# ST-LinkV2.net
KiCad netlist of a schematic drawn in Altium Designer
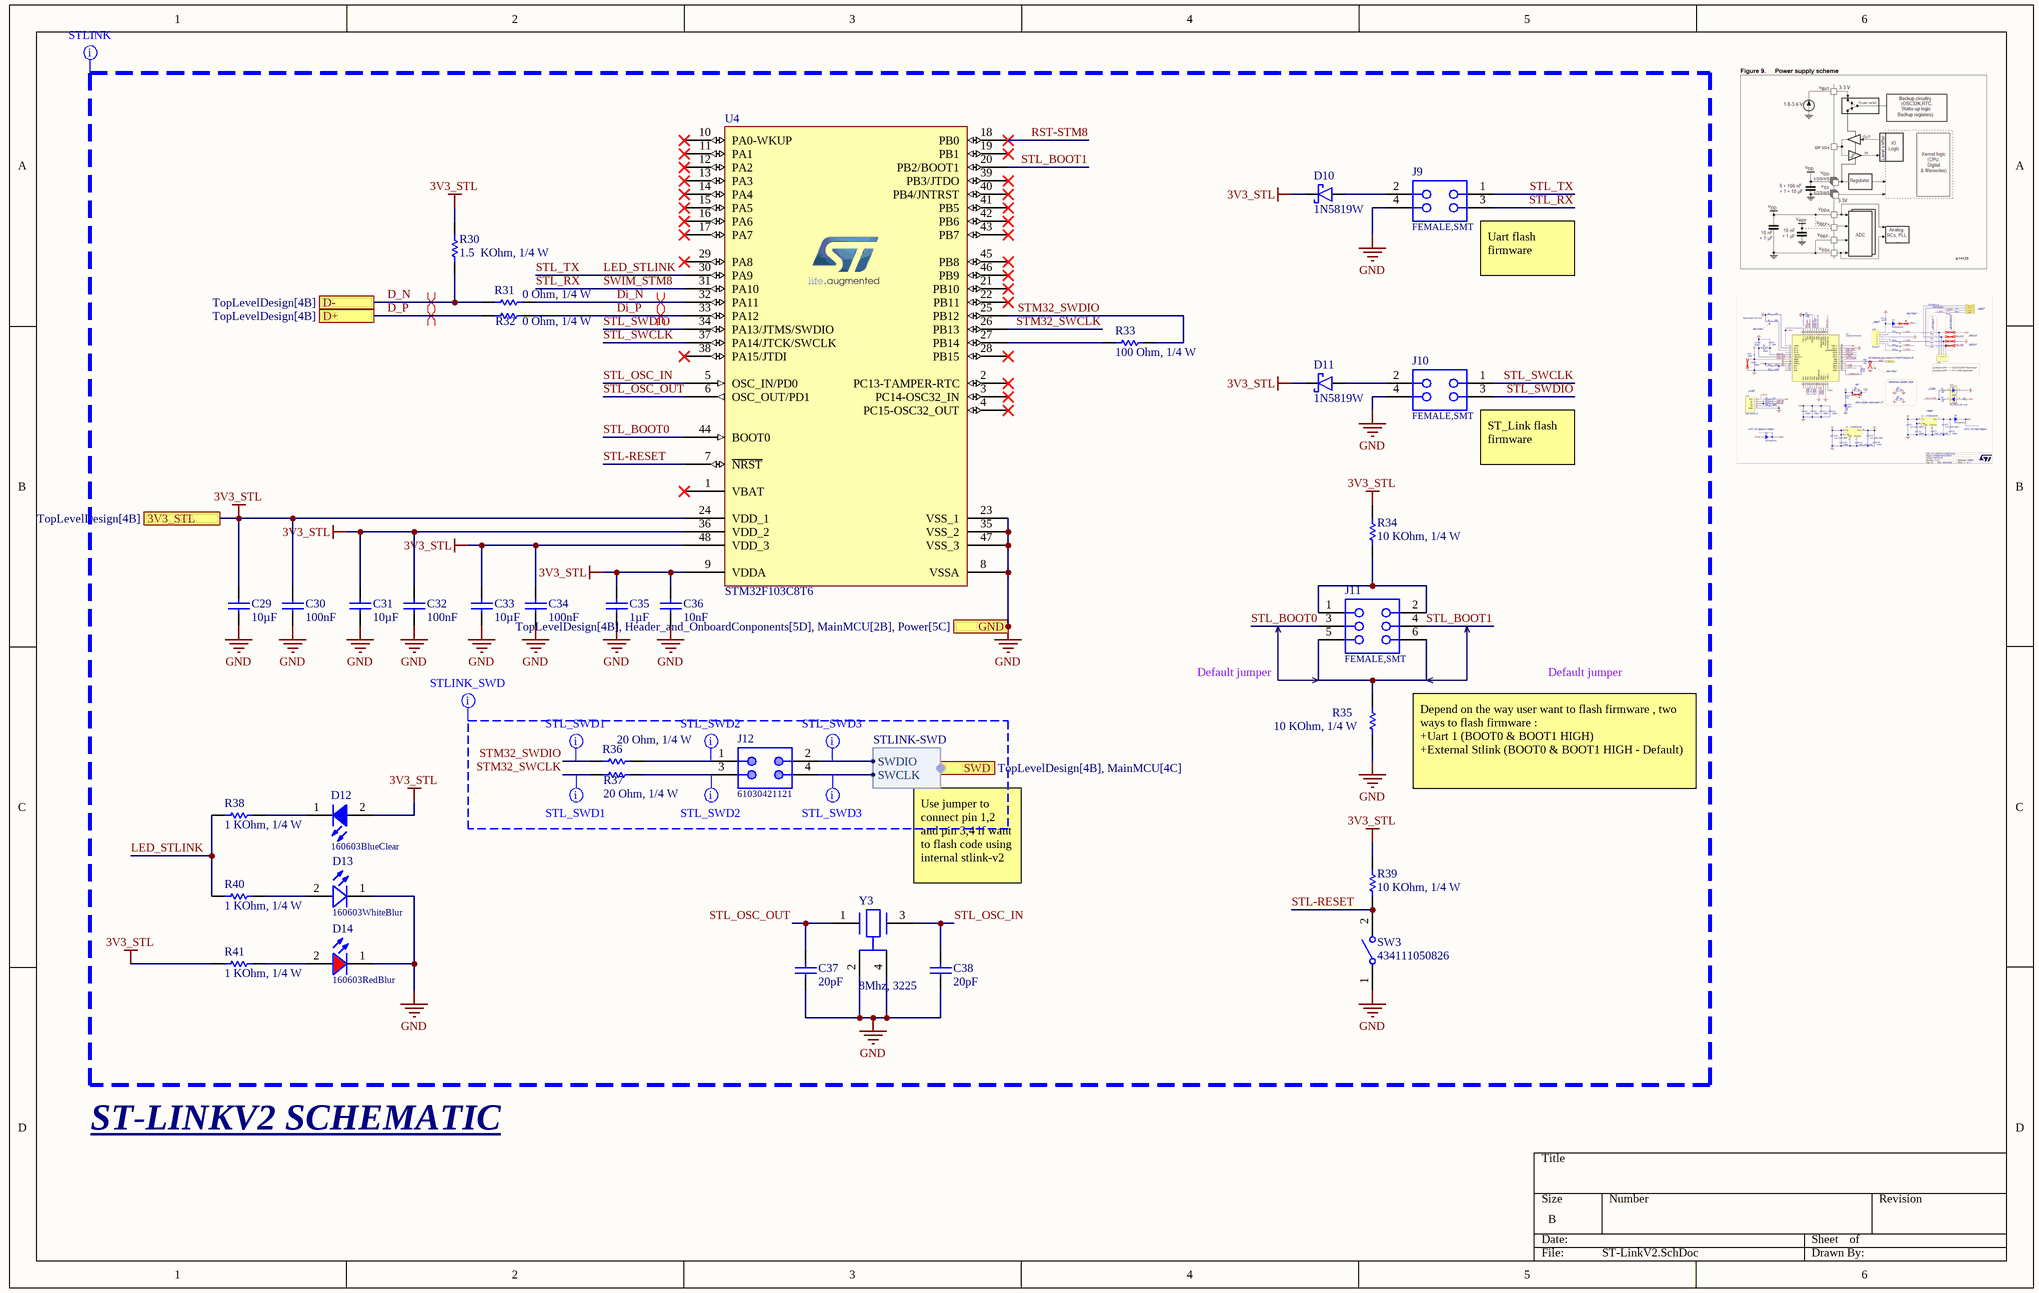
[diagram p0: ST-LinkV2.SchDoc]

(export (version "E")
  (design (tool "Eeschema 10.0.6"))
  (components
    (comp (ref "C29")
      (value "10µF")
      (footprint "CAP_0603")
      (description "CAP, size 0603, 10 uF, 10 VDC")
      (fields
        (field (name "TOLERANCE") "10%")
        (field (name "Comment") "0106031061010")
        (field (name "SOURCE") "Capacitor_0603_10_percent.SchLib")
      )
      (libsource (lib "Tin Tran") (part "010603475106.3"))
    )
    (comp (ref "C30")
      (value "100nF")
      (footprint "CAP_0603")
      (description "CAP, size 0603, 100 nF, 50 VDC")
      (fields
        (field (name "TOLERANCE") "10%")
        (field (name "Comment") "0106031041050")
        (field (name "SOURCE") "Capacitor_0603_10_percent.SchLib")
      )
      (libsource (lib "Tin Tran") (part "010603475106.3"))
    )
    (comp (ref "C31")
      (value "10µF")
      (footprint "CAP_0603")
      (description "CAP, size 0603, 10 uF, 10 VDC")
      (fields
        (field (name "TOLERANCE") "10%")
        (field (name "Comment") "0106031061010")
        (field (name "SOURCE") "Capacitor_0603_10_percent.SchLib")
      )
      (libsource (lib "Tin Tran") (part "010603475106.3"))
    )
    (comp (ref "C32")
      (value "100nF")
      (footprint "CAP_0603")
      (description "CAP, size 0603, 100 nF, 50 VDC")
      (fields
        (field (name "TOLERANCE") "10%")
        (field (name "Comment") "0106031041050")
        (field (name "SOURCE") "Capacitor_0603_10_percent.SchLib")
      )
      (libsource (lib "Tin Tran") (part "010603475106.3"))
    )
    (comp (ref "C33")
      (value "10µF")
      (footprint "CAP_0603")
      (description "CAP, size 0603, 10 uF, 10 VDC")
      (fields
        (field (name "TOLERANCE") "10%")
        (field (name "Comment") "0106031061010")
        (field (name "SOURCE") "Capacitor_0603_10_percent.SchLib")
      )
      (libsource (lib "Tin Tran") (part "010603475106.3"))
    )
    (comp (ref "C34")
      (value "100nF")
      (footprint "CAP_0603")
      (description "CAP, size 0603, 100 nF, 50 VDC")
      (fields
        (field (name "TOLERANCE") "10%")
        (field (name "Comment") "0106031041050")
        (field (name "SOURCE") "Capacitor_0603_10_percent.SchLib")
      )
      (libsource (lib "Tin Tran") (part "010603475106.3"))
    )
    (comp (ref "C35")
      (value "1µF")
      (footprint "CAP_0603")
      (description "CAP, size 0603, 1 uF, 16 VDC")
      (fields
        (field (name "TOLERANCE") "10%")
        (field (name "Comment") "0106031051016")
        (field (name "SOURCE") "Capacitor_0603_10_percent.SchLib")
      )
      (libsource (lib "Tin Tran") (part "010603475106.3"))
    )
    (comp (ref "C36")
      (value "10nF")
      (footprint "CAP_0603")
      (description "CAP, size 0603, 10 nF, 50 VDC")
      (fields
        (field (name "TOLERANCE") "5%")
        (field (name "Comment") "0106031030550")
        (field (name "SOURCE") "Capacitor_0603_5_percent.SchLib")
      )
      (libsource (lib "Tin Tran") (part "0106036820550"))
    )
    (comp (ref "C37")
      (value "20pF")
      (footprint "CAP_0603")
      (description "CAP, size 0603, 20 pF, 50 VDC")
      (fields
        (field (name "TOLERANCE") "5%")
        (field (name "Comment") "0106031000550")
        (field (name "SOURCE") "Capacitor_0603_5_percent.SchLib")
      )
      (libsource (lib "Tin Tran") (part "0106036820550"))
    )
    (comp (ref "C38")
      (value "20pF")
      (footprint "CAP_0603")
      (description "CAP, size 0603, 20 pF, 50 VDC")
      (fields
        (field (name "TOLERANCE") "5%")
        (field (name "Comment") "0106031000550")
        (field (name "SOURCE") "Capacitor_0603_5_percent.SchLib")
      )
      (libsource (lib "Tin Tran") (part "0106036820550"))
    )
    (comp (ref "D10") (value "1N5819W") (footprint "1N5819W") (libsource (lib "Tin Tran") (part "1N5819W")))
    (comp (ref "D11") (value "1N5819W") (footprint "1N5819W") (libsource (lib "Tin Tran") (part "1N5819W")))
    (comp (ref "D12")
      (value "160603BlueClear")
      (footprint "WL-SMCW_0603_H=0.7mm")
      (description "WL-SMCW SMT Mono-color Chip LED Waterclear, size 0603, Blue, 3.2V, 140deg")
      (libsource (lib "Tin Tran") (part "160603BlueClear"))
    )
    (comp (ref "D13")
      (value "160603WhiteBlur")
      (footprint "WL-SMCW_0603_H=0.7mm")
      (description "WL-SMCW SMT Mono-color Chip LED Blur, size 0603, White")
      (libsource (lib "Tin Tran") (part "160603WhiteClear"))
    )
    (comp (ref "D14")
      (value "160603RedBlur")
      (footprint "WL-SMCW_0603_H=0.7mm")
      (description "WL-SMCW SMT Mono-color Chip LED Blur, size 0603, Red, 2V, 140deg")
      (libsource (lib "Tin Tran") (part "160603RedClear"))
    )
    (comp (ref "J9")
      (value "FEMALE,SMT")
      (footprint "61000421821")
      (description "WR-PHD Socket Header, SMT, pitch 2.54mm, Dual Row, Vertical, 4p")
      (fields
        (field (name "MANUFACTURER") "Wurth Elektronik")
        (field (name "MANUFACTURER PART NUMBER") "61000421821")
      )
      (libsource (lib "Tin Tran") (part "61000421821"))
    )
    (comp (ref "J10")
      (value "FEMALE,SMT")
      (footprint "61000421821")
      (description "WR-PHD Socket Header, SMT, pitch 2.54mm, Dual Row, Vertical, 4p")
      (fields
        (field (name "MANUFACTURER") "Wurth Elektronik")
        (field (name "MANUFACTURER PART NUMBER") "61000421821")
      )
      (libsource (lib "Tin Tran") (part "61000421821"))
    )
    (comp (ref "J11")
      (value "FEMALE,SMT")
      (footprint "61030621821")
      (description "WR-PHD Socket Header, SMT, pitch 2.54mm, Dual Row, Vertical, 6p")
      (fields
        (field (name "MANUFACTURER PART NUMBER") "61030621821")
        (field (name "MANUFACTURER") "Wurth Elektronik")
      )
      (libsource (lib "Tin Tran") (part "613006243121"))
    )
    (comp (ref "J12")
      (value "61030421121")
      (footprint "61030421121")
      (description "WR-PHD Pin Header, SMT, pitch 2.54mm, Dual Row, Vertical, 4p")
      (fields (field (name "MANUFACTURER") "Wurth Elektronik"))
      (libsource (lib "Tin Tran") (part "61300421121"))
    )
    (comp (ref "R30")
      (value "1.5  KOhm, 1/4 W")
      (footprint "resistor_0603")
      (description "RES, size 0603, 1.5  KOhm, 1/4 W")
      (fields (field (name "Comment") "0006031521"))
      (libsource (lib "Tin Tran") (part "00060371541"))
    )
    (comp (ref "R31")
      (value "0 Ohm, 1/4 W")
      (footprint "resistor_0603")
      (description "RES, size 0603, 0 Ohm, 1/4 W")
      (fields (field (name "Comment") "0006030001"))
      (libsource (lib "Tin Tran") (part "00060371541"))
    )
    (comp (ref "R32")
      (value "0 Ohm, 1/4 W")
      (footprint "resistor_0603")
      (description "RES, size 0603, 0 Ohm, 1/4 W")
      (fields (field (name "Comment") "0006030001"))
      (libsource (lib "Tin Tran") (part "00060371541"))
    )
    (comp (ref "R33")
      (value "100 Ohm, 1/4 W")
      (footprint "resistor_0603")
      (description "RES, size 0603, 100 Ohm, 1/4 W")
      (fields (field (name "Comment") "0006031011"))
      (libsource (lib "Tin Tran") (part "00060371541"))
    )
    (comp (ref "R34")
      (value "10 KOhm, 1/4 W")
      (footprint "resistor_0603")
      (description "RES, size 0603, 10 KOhm, 1/4 W")
      (fields (field (name "Comment") "0006031031"))
      (libsource (lib "Tin Tran") (part "00060371541"))
    )
    (comp (ref "R35")
      (value "10 KOhm, 1/4 W")
      (footprint "resistor_0603")
      (description "RES, size 0603, 10 KOhm, 1/4 W")
      (fields (field (name "Comment") "0006031031"))
      (libsource (lib "Tin Tran") (part "00060371541"))
    )
    (comp (ref "R36")
      (value "20 Ohm, 1/4 W")
      (footprint "resistor_0603")
      (description "RES, size 0603, 20 Ohm, 1/4 W")
      (fields (field (name "Comment") "0006032001"))
      (libsource (lib "Tin Tran") (part "00060371541"))
    )
    (comp (ref "R37")
      (value "20 Ohm, 1/4 W")
      (footprint "resistor_0603")
      (description "RES, size 0603, 20 Ohm, 1/4 W")
      (fields (field (name "Comment") "0006032001"))
      (libsource (lib "Tin Tran") (part "00060371541"))
    )
    (comp (ref "R38")
      (value "1 KOhm, 1/4 W")
      (footprint "resistor_0603")
      (description "RES, size 0603, 1 KOhm, 1/4 W")
      (fields (field (name "Comment") "0006031021"))
      (libsource (lib "Tin Tran") (part "00060371541"))
    )
    (comp (ref "R39")
      (value "10 KOhm, 1/4 W")
      (footprint "resistor_0603")
      (description "RES, size 0603, 10 KOhm, 1/4 W")
      (fields (field (name "Comment") "0006031031"))
      (libsource (lib "Tin Tran") (part "00060371541"))
    )
    (comp (ref "R40")
      (value "1 KOhm, 1/4 W")
      (footprint "resistor_0603")
      (description "RES, size 0603, 1 KOhm, 1/4 W")
      (fields (field (name "Comment") "0006031021"))
      (libsource (lib "Tin Tran") (part "00060371541"))
    )
    (comp (ref "R41")
      (value "1 KOhm, 1/4 W")
      (footprint "resistor_0603")
      (description "RES, size 0603, 1 KOhm, 1/4 W")
      (fields (field (name "Comment") "0006031021"))
      (libsource (lib "Tin Tran") (part "00060371541"))
    )
    (comp (ref "SW3")
      (value "434111050826")
      (footprint "WS-TASV_L6W3.5H5_4341x10508x6")
      (description "WS-TASV SMT Tact Switch, L6 x W3.5 x H5mm, 260g, SPST-NO, 12V, 50mA")
      (fields (field (name "MANUFACTURER") "Wurth Elektronik"))
      (libsource (lib "Tin Tran") (part "434111050826"))
    )
    (comp (ref "U4")
      (value "STM32F103C8T6")
      (footprint "STM32F103C8T6")
      (description "ARM Microcontrollers - MCU 32BIT Cortex M3 64KB 20KB RAM 2X12 ADC")
      (fields (field (name "MANUFACTURER") "STM"))
      (libsource (lib "Tin Tran") (part "STM32F103C8T6"))
    )
    (comp (ref "Y3")
      (value "8Mhz, 3225")
      (footprint "FP-NX3225SA-MFG")
      (description "CRYSTAL 25.0000MHZ 8PF SMD")
      (fields
        (field (name "OCTOPART") "https://octopart.com/nx3225sa-25.000m-std-crs-2-ndk-51374293")
        (field (name "TOLERANCE") "15ppm")
      )
      (libsource (lib "Tin Tran") (part "CMP-200220-000002-1"))
    )
  )
  (nets
    (net (code "2") (name "/D_N") (class "Default")
      (node (ref "R30") (pin "1") (pinfunction "1_1") (pintype "passive"))
      (node (ref "R31") (pin "1") (pinfunction "1_1") (pintype "passive"))
    )
    (net (code "3") (name "/D_P") (class "Default")
      (node (ref "R32") (pin "1") (pinfunction "1_1") (pintype "passive"))
    )
    (net (code "4") (name "/Di_N") (class "Default")
      (node (ref "R31") (pin "2") (pinfunction "2_2") (pintype "passive"))
      (node (ref "U4") (pin "32") (pinfunction "PA11_32") (pintype "bidirectional"))
    )
    (net (code "5") (name "/Di_P") (class "Default")
      (node (ref "R32") (pin "2") (pinfunction "2_2") (pintype "passive"))
      (node (ref "U4") (pin "33") (pinfunction "PA12_33") (pintype "bidirectional"))
    )
    (net (code "6") (name "/LED_STLINK") (class "Default")
      (node (ref "J9") (pin "1") (pinfunction "1_1") (pintype "passive"))
      (node (ref "R38") (pin "1") (pinfunction "1_1") (pintype "passive"))
      (node (ref "R40") (pin "1") (pinfunction "1_1") (pintype "passive"))
      (node (ref "U4") (pin "30") (pinfunction "PA9_30") (pintype "bidirectional"))
    )
    (net (code "7") (name "/RST-STM8") (class "Default")
      (node (ref "U4") (pin "18") (pinfunction "PB0_18") (pintype "bidirectional+no_connect"))
    )
    (net (code "8") (name "/STL-RESET") (class "Default")
      (node (ref "R39") (pin "1") (pinfunction "1_1") (pintype "passive"))
      (node (ref "SW3") (pin "2") (pinfunction "2_2") (pintype "passive"))
      (node (ref "U4") (pin "7") (pinfunction "~{NRST}_7") (pintype "bidirectional"))
    )
    (net (code "9") (name "/STL_BOOT0") (class "Default")
      (node (ref "J11") (pin "3") (pinfunction "3_3") (pintype "passive"))
      (node (ref "U4") (pin "44") (pinfunction "BOOT0_44") (pintype "input"))
    )
    (net (code "10") (name "/STL_BOOT1") (class "Default")
      (node (ref "J11") (pin "4") (pinfunction "4_4") (pintype "passive"))
      (node (ref "U4") (pin "20") (pinfunction "PB2/BOOT1_20") (pintype "bidirectional"))
    )
    (net (code "11") (name "/STL_OSC_IN") (class "Default")
      (node (ref "C38") (pin "2") (pinfunction "2_2") (pintype "passive"))
      (node (ref "U4") (pin "5") (pinfunction "OSC_IN/PD0_5") (pintype "input"))
      (node (ref "Y3") (pin "3") (pinfunction "3_3") (pintype "passive"))
    )
    (net (code "12") (name "/STL_OSC_OUT") (class "Default")
      (node (ref "C37") (pin "2") (pinfunction "2_2") (pintype "passive"))
      (node (ref "U4") (pin "6") (pinfunction "OSC_OUT/PD1_6") (pintype "output"))
      (node (ref "Y3") (pin "1") (pinfunction "1_1") (pintype "passive"))
    )
    (net (code "13") (name "/STL_RX") (class "Default")
      (node (ref "J9") (pin "3") (pinfunction "3_3") (pintype "passive"))
      (node (ref "U4") (pin "31") (pinfunction "PA10_31") (pintype "bidirectional"))
    )
    (net (code "14") (name "/STL_SWCLK") (class "Default")
      (node (ref "J10") (pin "1") (pinfunction "1_1") (pintype "passive"))
      (node (ref "U4") (pin "37") (pinfunction "PA14/JTCK/SWCLK_37") (pintype "bidirectional"))
    )
    (net (code "15") (name "/STL_SWDIO") (class "Default")
      (node (ref "J10") (pin "3") (pinfunction "3_3") (pintype "passive"))
      (node (ref "U4") (pin "34") (pinfunction "PA13/JTMS/SWDIO_34") (pintype "bidirectional"))
    )
    (net (code "16") (name "/STM32_SWCLK") (class "Default")
      (node (ref "R37") (pin "1") (pinfunction "1_1") (pintype "passive"))
      (node (ref "U4") (pin "26") (pinfunction "PB13_26") (pintype "bidirectional"))
    )
    (net (code "17") (name "/STM32_SWDIO") (class "Default")
      (node (ref "R33") (pin "1") (pinfunction "1_1") (pintype "passive"))
      (node (ref "R36") (pin "1") (pinfunction "1_1") (pintype "passive"))
      (node (ref "U4") (pin "25") (pinfunction "PB12_25") (pintype "bidirectional"))
    )
    (net (code "18") (name "/SWCLK") (class "Default")
      (node (ref "J12") (pin "4") (pinfunction "4_4") (pintype "passive"))
    )
    (net (code "19") (name "/SWDIO") (class "Default")
      (node (ref "J12") (pin "2") (pinfunction "2_2") (pintype "passive"))
    )
    (net (code "21") (name "3V3_STL") (class "Default")
      (node (ref "C29") (pin "2") (pinfunction "2_2") (pintype "passive"))
      (node (ref "C30") (pin "2") (pinfunction "2_2") (pintype "passive"))
      (node (ref "C31") (pin "2") (pinfunction "2_2") (pintype "passive"))
      (node (ref "C32") (pin "2") (pinfunction "2_2") (pintype "passive"))
      (node (ref "C33") (pin "2") (pinfunction "2_2") (pintype "passive"))
      (node (ref "C34") (pin "2") (pinfunction "2_2") (pintype "passive"))
      (node (ref "C35") (pin "2") (pinfunction "2_2") (pintype "passive"))
      (node (ref "C36") (pin "2") (pinfunction "2_2") (pintype "passive"))
      (node (ref "D10") (pin "K") (pinfunction "K_K") (pintype "passive"))
      (node (ref "D11") (pin "K") (pinfunction "K_K") (pintype "passive"))
      (node (ref "D12") (pin "2") (pinfunction "A_2") (pintype "passive"))
      (node (ref "R30") (pin "2") (pinfunction "2_2") (pintype "passive"))
      (node (ref "R34") (pin "2") (pinfunction "2_2") (pintype "passive"))
      (node (ref "R39") (pin "2") (pinfunction "2_2") (pintype "passive"))
      (node (ref "R41") (pin "1") (pinfunction "1_1") (pintype "passive"))
      (node (ref "U4") (pin "24") (pinfunction "VDD_1_24") (pintype "power_in"))
      (node (ref "U4") (pin "36") (pinfunction "VDD_2_36") (pintype "power_in"))
      (node (ref "U4") (pin "48") (pinfunction "VDD_3_48") (pintype "power_in"))
      (node (ref "U4") (pin "9") (pinfunction "VDDA_9") (pintype "power_in"))
    )
    (net (code "22") (name "GND") (class "Default")
      (node (ref "C29") (pin "1") (pinfunction "1_1") (pintype "passive"))
      (node (ref "C30") (pin "1") (pinfunction "1_1") (pintype "passive"))
      (node (ref "C31") (pin "1") (pinfunction "1_1") (pintype "passive"))
      (node (ref "C32") (pin "1") (pinfunction "1_1") (pintype "passive"))
      (node (ref "C33") (pin "1") (pinfunction "1_1") (pintype "passive"))
      (node (ref "C34") (pin "1") (pinfunction "1_1") (pintype "passive"))
      (node (ref "C35") (pin "1") (pinfunction "1_1") (pintype "passive"))
      (node (ref "C36") (pin "1") (pinfunction "1_1") (pintype "passive"))
      (node (ref "C37") (pin "1") (pinfunction "1_1") (pintype "passive"))
      (node (ref "C38") (pin "1") (pinfunction "1_1") (pintype "passive"))
      (node (ref "D13") (pin "1") (pinfunction "K_1") (pintype "passive"))
      (node (ref "D14") (pin "1") (pinfunction "K_1") (pintype "passive"))
      (node (ref "J10") (pin "4") (pinfunction "4_4") (pintype "passive"))
      (node (ref "J9") (pin "4") (pinfunction "4_4") (pintype "passive"))
      (node (ref "R35") (pin "1") (pinfunction "1_1") (pintype "passive"))
      (node (ref "SW3") (pin "1") (pinfunction "1_1") (pintype "passive"))
      (node (ref "U4") (pin "23") (pinfunction "VSS_1_23") (pintype "power_in"))
      (node (ref "U4") (pin "35") (pinfunction "VSS_2_35") (pintype "power_in"))
      (node (ref "U4") (pin "47") (pinfunction "VSS_3_47") (pintype "power_in"))
      (node (ref "U4") (pin "8") (pinfunction "VSSA_8") (pintype "power_in"))
      (node (ref "Y3") (pin "2") (pinfunction "GND_2") (pintype "power_in"))
      (node (ref "Y3") (pin "4") (pinfunction "GND_4") (pintype "power_in"))
    )
    (net (code "23") (name "Net-(D10-PadA)") (class "Default")
      (node (ref "D10") (pin "A") (pinfunction "A_A") (pintype "passive"))
      (node (ref "J9") (pin "2") (pinfunction "2_2") (pintype "passive"))
    )
    (net (code "24") (name "Net-(D11-PadA)") (class "Default")
      (node (ref "D11") (pin "A") (pinfunction "A_A") (pintype "passive"))
      (node (ref "J10") (pin "2") (pinfunction "2_2") (pintype "passive"))
    )
    (net (code "25") (name "Net-(D12-K)") (class "Default")
      (node (ref "D12") (pin "1") (pinfunction "K_1") (pintype "passive"))
      (node (ref "R38") (pin "2") (pinfunction "2_2") (pintype "passive"))
    )
    (net (code "26") (name "Net-(D13-A)") (class "Default")
      (node (ref "D13") (pin "2") (pinfunction "A_2") (pintype "passive"))
      (node (ref "R40") (pin "2") (pinfunction "2_2") (pintype "passive"))
    )
    (net (code "27") (name "Net-(D14-A)") (class "Default")
      (node (ref "D14") (pin "2") (pinfunction "A_2") (pintype "passive"))
      (node (ref "R41") (pin "2") (pinfunction "2_2") (pintype "passive"))
    )
    (net (code "28") (name "Net-(J11-Pad1)") (class "Default")
      (node (ref "J11") (pin "1") (pinfunction "1_1") (pintype "passive"))
      (node (ref "J11") (pin "2") (pinfunction "2_2") (pintype "passive"))
      (node (ref "R34") (pin "1") (pinfunction "1_1") (pintype "passive"))
    )
    (net (code "29") (name "Net-(J11-Pad5)") (class "Default")
      (node (ref "J11") (pin "5") (pinfunction "5_5") (pintype "passive"))
      (node (ref "J11") (pin "6") (pinfunction "6_6") (pintype "passive"))
      (node (ref "R35") (pin "2") (pinfunction "2_2") (pintype "passive"))
    )
    (net (code "30") (name "Net-(J12-Pad1)") (class "Default")
      (node (ref "J12") (pin "1") (pinfunction "1_1") (pintype "passive"))
      (node (ref "R36") (pin "2") (pinfunction "2_2") (pintype "passive"))
    )
    (net (code "31") (name "Net-(J12-Pad3)") (class "Default")
      (node (ref "J12") (pin "3") (pinfunction "3_3") (pintype "passive"))
      (node (ref "R37") (pin "2") (pinfunction "2_2") (pintype "passive"))
    )
    (net (code "32") (name "Net-(U4-PB14)") (class "Default")
      (node (ref "R33") (pin "2") (pinfunction "2_2") (pintype "passive"))
      (node (ref "U4") (pin "27") (pinfunction "PB14_27") (pintype "bidirectional"))
    )
    (net (code "33") (name "unconnected-(U4-PA0-WKUP-Pad10)") (class "Default")
      (node (ref "U4") (pin "10") (pinfunction "PA0-WKUP_10") (pintype "bidirectional+no_connect"))
    )
    (net (code "34") (name "unconnected-(U4-PA1-Pad11)") (class "Default")
      (node (ref "U4") (pin "11") (pinfunction "PA1_11") (pintype "bidirectional+no_connect"))
    )
    (net (code "35") (name "unconnected-(U4-PA2-Pad12)") (class "Default")
      (node (ref "U4") (pin "12") (pinfunction "PA2_12") (pintype "bidirectional+no_connect"))
    )
    (net (code "36") (name "unconnected-(U4-PA3-Pad13)") (class "Default")
      (node (ref "U4") (pin "13") (pinfunction "PA3_13") (pintype "bidirectional+no_connect"))
    )
    (net (code "37") (name "unconnected-(U4-PA4-Pad14)") (class "Default")
      (node (ref "U4") (pin "14") (pinfunction "PA4_14") (pintype "bidirectional+no_connect"))
    )
    (net (code "38") (name "unconnected-(U4-PA5-Pad15)") (class "Default")
      (node (ref "U4") (pin "15") (pinfunction "PA5_15") (pintype "bidirectional+no_connect"))
    )
    (net (code "39") (name "unconnected-(U4-PA6-Pad16)") (class "Default")
      (node (ref "U4") (pin "16") (pinfunction "PA6_16") (pintype "bidirectional+no_connect"))
    )
    (net (code "40") (name "unconnected-(U4-PA7-Pad17)") (class "Default")
      (node (ref "U4") (pin "17") (pinfunction "PA7_17") (pintype "bidirectional+no_connect"))
    )
    (net (code "41") (name "unconnected-(U4-PA8-Pad29)") (class "Default")
      (node (ref "U4") (pin "29") (pinfunction "PA8_29") (pintype "bidirectional+no_connect"))
    )
    (net (code "42") (name "unconnected-(U4-PA15{slash}JTDI-Pad38)") (class "Default")
      (node (ref "U4") (pin "38") (pinfunction "PA15/JTDI_38") (pintype "bidirectional+no_connect"))
    )
    (net (code "43") (name "unconnected-(U4-PB1-Pad19)") (class "Default")
      (node (ref "U4") (pin "19") (pinfunction "PB1_19") (pintype "bidirectional+no_connect"))
    )
    (net (code "44") (name "unconnected-(U4-PB3{slash}JTDO-Pad39)") (class "Default")
      (node (ref "U4") (pin "39") (pinfunction "PB3/JTDO_39") (pintype "bidirectional+no_connect"))
    )
    (net (code "45") (name "unconnected-(U4-PB4{slash}JNTRST-Pad40)") (class "Default")
      (node (ref "U4") (pin "40") (pinfunction "PB4/JNTRST_40") (pintype "bidirectional+no_connect"))
    )
    (net (code "46") (name "unconnected-(U4-PB5-Pad41)") (class "Default")
      (node (ref "U4") (pin "41") (pinfunction "PB5_41") (pintype "bidirectional+no_connect"))
    )
    (net (code "47") (name "unconnected-(U4-PB6-Pad42)") (class "Default")
      (node (ref "U4") (pin "42") (pinfunction "PB6_42") (pintype "bidirectional+no_connect"))
    )
    (net (code "48") (name "unconnected-(U4-PB7-Pad43)") (class "Default")
      (node (ref "U4") (pin "43") (pinfunction "PB7_43") (pintype "bidirectional+no_connect"))
    )
    (net (code "49") (name "unconnected-(U4-PB8-Pad45)") (class "Default")
      (node (ref "U4") (pin "45") (pinfunction "PB8_45") (pintype "bidirectional+no_connect"))
    )
    (net (code "50") (name "unconnected-(U4-PB9-Pad46)") (class "Default")
      (node (ref "U4") (pin "46") (pinfunction "PB9_46") (pintype "bidirectional+no_connect"))
    )
    (net (code "51") (name "unconnected-(U4-PB10-Pad21)") (class "Default")
      (node (ref "U4") (pin "21") (pinfunction "PB10_21") (pintype "bidirectional+no_connect"))
    )
    (net (code "52") (name "unconnected-(U4-PB11-Pad22)") (class "Default")
      (node (ref "U4") (pin "22") (pinfunction "PB11_22") (pintype "bidirectional+no_connect"))
    )
    (net (code "53") (name "unconnected-(U4-PB15-Pad28)") (class "Default")
      (node (ref "U4") (pin "28") (pinfunction "PB15_28") (pintype "bidirectional+no_connect"))
    )
    (net (code "54") (name "unconnected-(U4-PC13-TAMPER-RTC-Pad2)") (class "Default")
      (node (ref "U4") (pin "2") (pinfunction "PC13-TAMPER-RTC_2") (pintype "bidirectional+no_connect"))
    )
    (net (code "55") (name "unconnected-(U4-PC14-OSC32_IN-Pad3)") (class "Default")
      (node (ref "U4") (pin "3") (pinfunction "PC14-OSC32_IN_3") (pintype "bidirectional+no_connect"))
    )
    (net (code "56") (name "unconnected-(U4-PC15-OSC32_OUT-Pad4)") (class "Default")
      (node (ref "U4") (pin "4") (pinfunction "PC15-OSC32_OUT_4") (pintype "bidirectional+no_connect"))
    )
    (net (code "57") (name "unconnected-(U4-VBAT-Pad1)") (class "Default")
      (node (ref "U4") (pin "1") (pinfunction "VBAT_1") (pintype "power_in+no_connect"))
    )
  )
)
